# CH32L103F8U-R0.net
KiCad netlist of a schematic drawn in Altium Designer
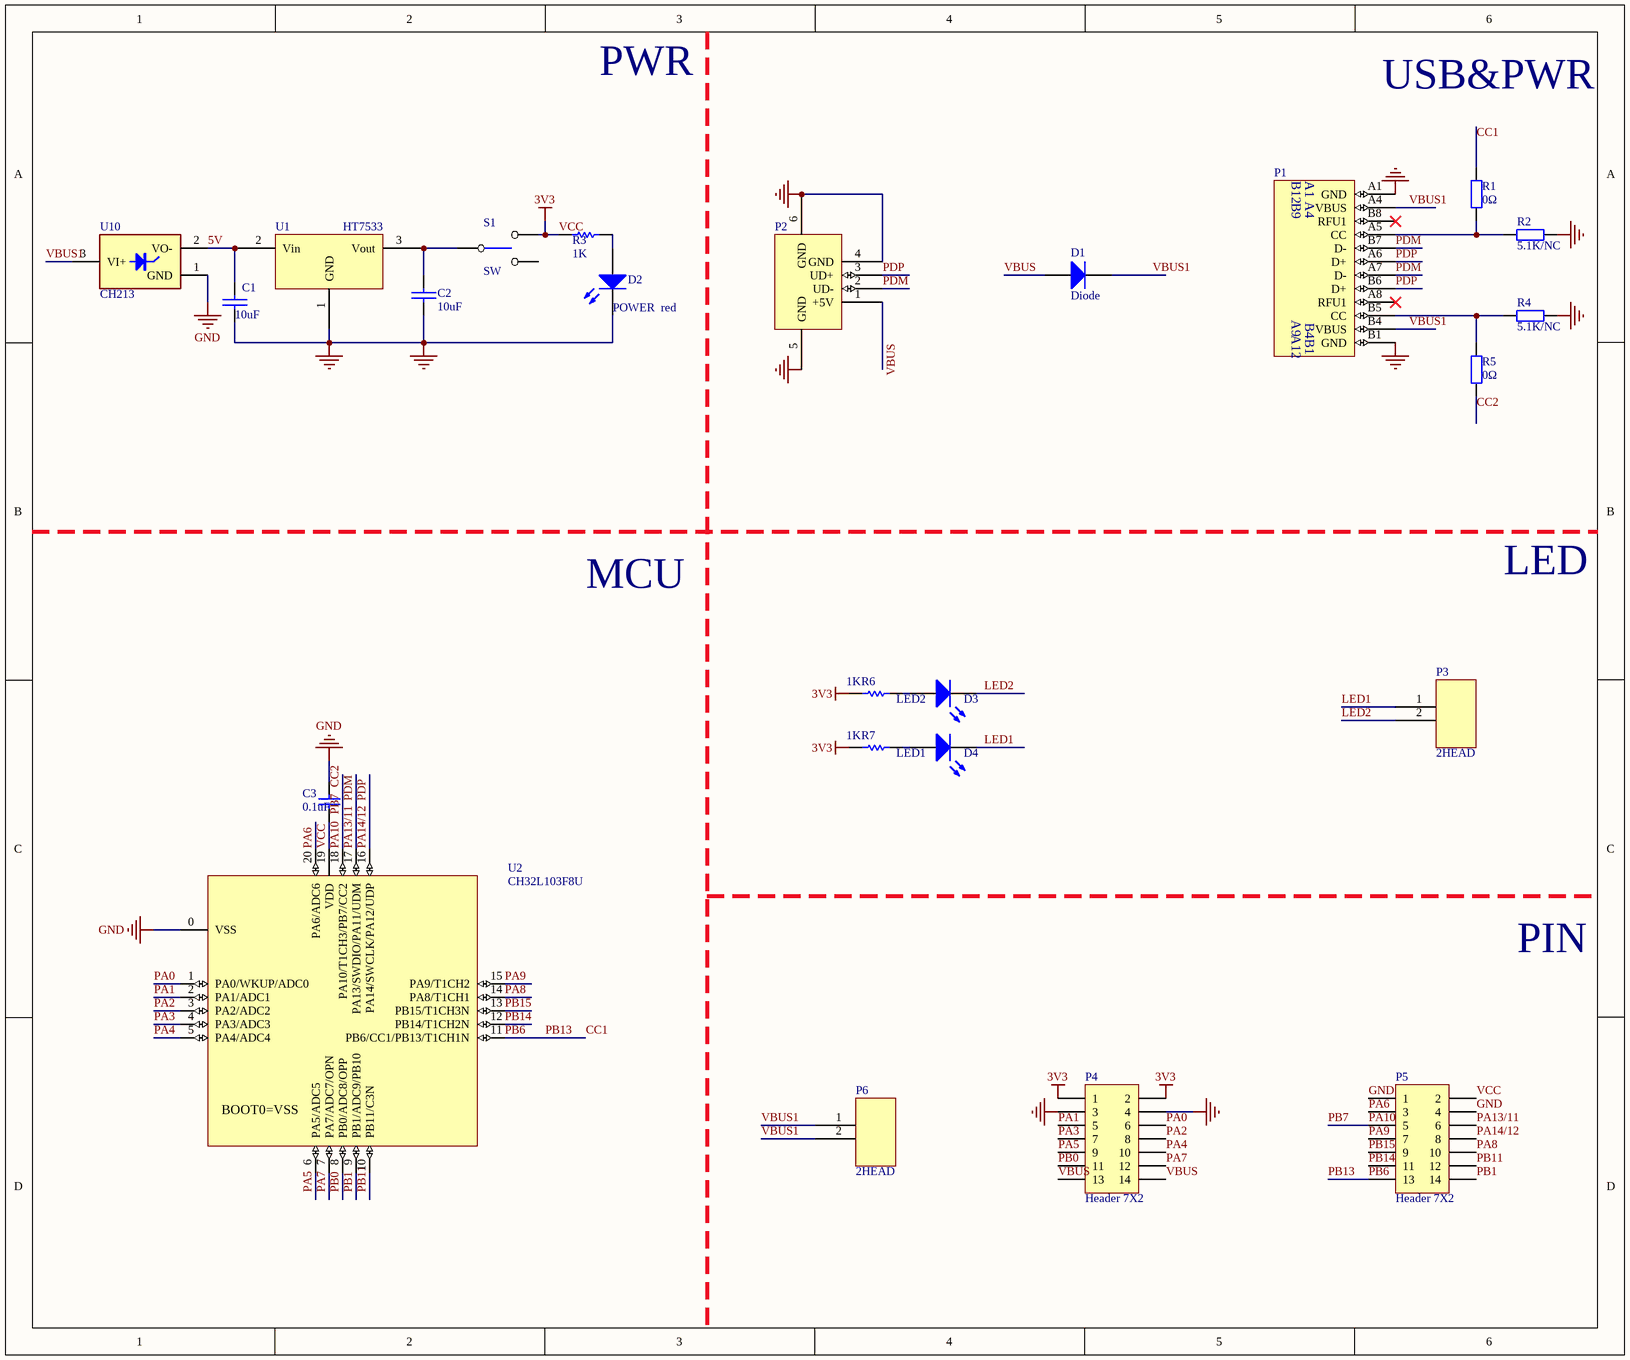
[diagram p0: CH32L103F8U-R0.SchDoc]

(export (version "E")
  (design (tool "Eeschema 10.0.6"))
  (components
    (comp (ref "C1")
      (value "10uF")
      (footprint "0603_C")
      (description "Capacitor")
      (libsource (lib "*") (part "CAP"))
    )
    (comp (ref "C2")
      (value "10uF")
      (footprint "0603_C")
      (description "Capacitor")
      (libsource (lib "*") (part "CAP"))
    )
    (comp (ref "C3")
      (value "0.1uF")
      (footprint "0603_C")
      (description "Capacitor")
      (fields (field (name "PUBLISHER") "Altium Limited"))
      (libsource (lib "*") (part "Cap"))
    )
    (comp (ref "D1")
      (value "Diode")
      (footprint "SOD-123")
      (description "Default Diode")
      (fields (field (name "PUBLISHER") "Altium Limited"))
      (libsource (lib "Miscellaneous Devices") (part "Diode"))
    )
    (comp (ref "D2")
      (value "POWER  red")
      (footprint "0603+")
      (description "Typical INFRARED GaAs LED")
      (fields (field (name "PUBLISHER") "Altium Limited"))
      (libsource (lib "*") (part "LED0"))
    )
    (comp (ref "D3")
      (value "LED2")
      (footprint "0603+")
      (description "Typical INFRARED GaAs LED")
      (fields (field (name "PUBLISHER") "Altium Limited"))
      (libsource (lib "*") (part "LED0"))
    )
    (comp (ref "D4")
      (value "LED1")
      (footprint "0603+")
      (description "Typical INFRARED GaAs LED")
      (fields (field (name "PUBLISHER") "Altium Limited"))
      (libsource (lib "*") (part "LED0"))
    )
    (comp (ref "P1")
      (value "TYPE-C")
      (footprint "TYPE-C-Receptacle-2.0")
      (libsource (lib "*") (part "TYPE-C1"))
    )
    (comp (ref "P2")
      (value "USB_A")
      (footprint "USBAF")
      (description "USB Port")
      (libsource (lib "*") (part "USB"))
    )
    (comp (ref "P3") (value "2HEAD") (footprint "SIP2-2.54mm") (libsource (lib "*") (part "2HEAD")))
    (comp (ref "P4")
      (value "Header 7X2")
      (footprint "IDC14-2.54mm")
      (description "Header, 7-Pin, Dual row")
      (fields (field (name "PUBLISHER") "Altium Limited"))
      (libsource (lib "Miscellaneous Connectors") (part "Header 7X2"))
    )
    (comp (ref "P5")
      (value "Header 7X2")
      (footprint "IDC14-2.54mm")
      (description "Header, 7-Pin, Dual row")
      (fields (field (name "PUBLISHER") "Altium Limited"))
      (libsource (lib "Miscellaneous Connectors") (part "Header 7X2"))
    )
    (comp (ref "P6") (value "2HEAD") (footprint "SIP2-2.54mm") (libsource (lib "*") (part "2HEAD")))
    (comp (ref "R1")
      (value "0Ω")
      (footprint "0603")
      (description "Resistor")
      (libsource (lib "") (part "Res2_1"))
    )
    (comp (ref "R2")
      (value "5.1K/NC")
      (footprint "0603")
      (description "Resistor")
      (libsource (lib "Miscellaneous Devices") (part "Res2"))
    )
    (comp (ref "R3")
      (value "1K")
      (footprint "0603")
      (description "Semiconductor Resistor")
      (libsource (lib "*") (part "Res Semi"))
    )
    (comp (ref "R4")
      (value "5.1K/NC")
      (footprint "0603")
      (description "Resistor")
      (libsource (lib "Miscellaneous Devices") (part "Res2"))
    )
    (comp (ref "R5")
      (value "0Ω")
      (footprint "0603")
      (description "Resistor")
      (libsource (lib "") (part "Res2_1"))
    )
    (comp (ref "R6")
      (value "1K")
      (footprint "0603")
      (description "Semiconductor Resistor")
      (libsource (lib "*") (part "Res Semi"))
    )
    (comp (ref "R7")
      (value "1K")
      (footprint "0603")
      (description "Semiconductor Resistor")
      (libsource (lib "*") (part "Res Semi"))
    )
    (comp (ref "S1") (value "SW") (footprint "SW1") (libsource (lib "*") (part "SW")))
    (comp (ref "U1")
      (value "HT7533")
      (footprint "SOT-89")
      (libsource (lib "wch_sch_others") (part "1117-3.3V"))
    )
    (comp (ref "U2")
      (value "CH32L103F8U")
      (footprint "QFN20_3X3")
      (description "RISC-V LMD-MCU, 96MHz, USB, Type-C/PD-5K1, CAN, OPA, lower power")
      (libsource (lib "CHXXX") (part "CH32L103F8U"))
    )
    (comp (ref "U10")
      (value "CH213")
      (footprint "SOT-23-3")
      (description "Ideal Diode 5V*1A")
      (libsource (lib "CHXXX") (part "CH213E"))
    )
  )
  (nets
    (net (code "1") (name "/5V") (class "Default")
      (node (ref "C1") (pin "1") (pinfunction "1_1") (pintype "passive"))
      (node (ref "U1") (pin "2") (pinfunction "Vin_2") (pintype "passive"))
      (node (ref "U10") (pin "2") (pinfunction "VO-_2") (pintype "power_in"))
    )
    (net (code "3") (name "/CC1") (class "Default")
      (node (ref "P5") (pin "13") (pinfunction "13_13") (pintype "passive"))
      (node (ref "R1") (pin "2") (pinfunction "2_2") (pintype "passive"))
      (node (ref "U2") (pin "11") (pinfunction "PB6/CC1/PB13/T1CH1N_11") (pintype "bidirectional"))
    )
    (net (code "4") (name "/CC2") (class "Default")
      (node (ref "P5") (pin "5") (pinfunction "5_5") (pintype "passive"))
      (node (ref "R5") (pin "1") (pinfunction "1_1") (pintype "passive"))
      (node (ref "U2") (pin "18") (pinfunction "PA10/T1CH3/PB7/CC2_18") (pintype "bidirectional"))
    )
    (net (code "5") (name "/LED1") (class "Default")
      (node (ref "D4") (pin "2") (pinfunction "K_2") (pintype "passive"))
      (node (ref "P3") (pin "1") (pintype "passive"))
    )
    (net (code "6") (name "/LED2") (class "Default")
      (node (ref "D3") (pin "2") (pinfunction "K_2") (pintype "passive"))
      (node (ref "P3") (pin "2") (pintype "passive"))
    )
    (net (code "7") (name "/PA0") (class "Default")
      (node (ref "P4") (pin "6") (pinfunction "6_6") (pintype "passive"))
      (node (ref "U2") (pin "1") (pinfunction "PA0/WKUP/ADC0_1") (pintype "bidirectional"))
    )
    (net (code "8") (name "/PA1") (class "Default")
      (node (ref "P4") (pin "5") (pinfunction "5_5") (pintype "passive"))
      (node (ref "U2") (pin "2") (pinfunction "PA1/ADC1_2") (pintype "bidirectional"))
    )
    (net (code "9") (name "/PA2") (class "Default")
      (node (ref "P4") (pin "8") (pinfunction "8_8") (pintype "passive"))
      (node (ref "U2") (pin "3") (pinfunction "PA2/ADC2_3") (pintype "bidirectional"))
    )
    (net (code "10") (name "/PA3") (class "Default")
      (node (ref "P4") (pin "7") (pinfunction "7_7") (pintype "passive"))
      (node (ref "U2") (pin "4") (pinfunction "PA3/ADC3_4") (pintype "bidirectional"))
    )
    (net (code "11") (name "/PA4") (class "Default")
      (node (ref "P4") (pin "10") (pinfunction "10_10") (pintype "passive"))
      (node (ref "U2") (pin "5") (pinfunction "PA4/ADC4_5") (pintype "bidirectional"))
    )
    (net (code "12") (name "/PA5") (class "Default")
      (node (ref "P4") (pin "9") (pinfunction "9_9") (pintype "passive"))
      (node (ref "U2") (pin "6") (pinfunction "PA5/ADC5_6") (pintype "bidirectional"))
    )
    (net (code "13") (name "/PA6") (class "Default")
      (node (ref "P5") (pin "3") (pinfunction "3_3") (pintype "passive"))
      (node (ref "U2") (pin "20") (pinfunction "PA6/ADC6_20") (pintype "bidirectional"))
    )
    (net (code "14") (name "/PA7") (class "Default")
      (node (ref "P4") (pin "12") (pinfunction "12_12") (pintype "passive"))
      (node (ref "U2") (pin "7") (pinfunction "PA7/ADC7/OPN_7") (pintype "bidirectional"))
    )
    (net (code "15") (name "/PA8") (class "Default")
      (node (ref "P5") (pin "10") (pinfunction "10_10") (pintype "passive"))
      (node (ref "U2") (pin "14") (pinfunction "PA8/T1CH1_14") (pintype "bidirectional"))
    )
    (net (code "16") (name "/PA9") (class "Default")
      (node (ref "P5") (pin "7") (pinfunction "7_7") (pintype "passive"))
      (node (ref "U2") (pin "15") (pinfunction "PA9/T1CH2_15") (pintype "bidirectional"))
    )
    (net (code "17") (name "/PA13{slash}11") (class "Default")
      (node (ref "P1") (pin "A7") (pinfunction "D-_A7") (pintype "bidirectional"))
      (node (ref "P1") (pin "B7") (pinfunction "D-_B7") (pintype "bidirectional"))
      (node (ref "P2") (pin "2") (pinfunction "UD-_2") (pintype "bidirectional"))
      (node (ref "P5") (pin "6") (pinfunction "6_6") (pintype "passive"))
      (node (ref "U2") (pin "17") (pinfunction "PA13/SWDIO/PA11/UDM_17") (pintype "bidirectional"))
    )
    (net (code "18") (name "/PA14{slash}12") (class "Default")
      (node (ref "P1") (pin "A6") (pinfunction "D+_A6") (pintype "bidirectional"))
      (node (ref "P1") (pin "B6") (pinfunction "D+_B6") (pintype "bidirectional"))
      (node (ref "P2") (pin "3") (pinfunction "UD+_3") (pintype "bidirectional"))
      (node (ref "P5") (pin "8") (pinfunction "8_8") (pintype "passive"))
      (node (ref "U2") (pin "16") (pinfunction "PA14/SWCLK/PA12/UDP_16") (pintype "bidirectional"))
    )
    (net (code "19") (name "/PB0") (class "Default")
      (node (ref "P4") (pin "11") (pinfunction "11_11") (pintype "passive"))
      (node (ref "U2") (pin "8") (pinfunction "PB0/ADC8/OPP_8") (pintype "bidirectional"))
    )
    (net (code "20") (name "/PB1") (class "Default")
      (node (ref "P5") (pin "14") (pinfunction "14_14") (pintype "passive"))
      (node (ref "U2") (pin "9") (pinfunction "PB1/ADC9/PB10_9") (pintype "bidirectional"))
    )
    (net (code "21") (name "/PB11") (class "Default")
      (node (ref "P5") (pin "12") (pinfunction "12_12") (pintype "passive"))
      (node (ref "U2") (pin "10") (pinfunction "PB11/C3N_10") (pintype "bidirectional"))
    )
    (net (code "22") (name "/PB14") (class "Default")
      (node (ref "P5") (pin "11") (pinfunction "11_11") (pintype "passive"))
      (node (ref "U2") (pin "12") (pinfunction "PB14/T1CH2N_12") (pintype "bidirectional"))
    )
    (net (code "23") (name "/PB15") (class "Default")
      (node (ref "P5") (pin "9") (pinfunction "9_9") (pintype "passive"))
      (node (ref "U2") (pin "13") (pinfunction "PB15/T1CH3N_13") (pintype "bidirectional"))
    )
    (net (code "24") (name "/VBUS") (class "Default")
      (node (ref "D1") (pin "1") (pinfunction "A_1") (pintype "passive"))
      (node (ref "P2") (pin "1") (pinfunction "+5V_1") (pintype "power_in"))
      (node (ref "P4") (pin "13") (pinfunction "13_13") (pintype "passive"))
      (node (ref "P4") (pin "14") (pinfunction "14_14") (pintype "passive"))
    )
    (net (code "25") (name "/VBUS1") (class "Default")
      (node (ref "D1") (pin "2") (pinfunction "K_2") (pintype "passive"))
      (node (ref "P1") (pin "A4") (pinfunction "VBUS_A4") (pintype "bidirectional"))
      (node (ref "P1") (pin "B4") (pinfunction "VBUS_B4") (pintype "bidirectional"))
      (node (ref "P6") (pin "1") (pintype "passive"))
      (node (ref "P6") (pin "2") (pintype "passive"))
      (node (ref "U10") (pin "3") (pinfunction "VI+_3") (pintype "power_in"))
    )
    (net (code "26") (name "3V3") (class "Default")
      (node (ref "C3") (pin "1") (pinfunction "1_1") (pintype "passive"))
      (node (ref "P4") (pin "1") (pinfunction "1_1") (pintype "passive"))
      (node (ref "P4") (pin "2") (pinfunction "2_2") (pintype "passive"))
      (node (ref "P5") (pin "2") (pinfunction "2_2") (pintype "passive"))
      (node (ref "R3") (pin "2") (pinfunction "2_2") (pintype "passive"))
      (node (ref "R6") (pin "1") (pinfunction "1_1") (pintype "passive"))
      (node (ref "R7") (pin "1") (pinfunction "1_1") (pintype "passive"))
      (node (ref "S1") (pin "3") (pinfunction "3_3") (pintype "passive"))
      (node (ref "U2") (pin "19") (pinfunction "VDD_19") (pintype "power_in"))
    )
    (net (code "27") (name "GND") (class "Default")
      (node (ref "C1") (pin "2") (pinfunction "2_2") (pintype "passive"))
      (node (ref "C2") (pin "2") (pinfunction "2_2") (pintype "passive"))
      (node (ref "C3") (pin "2") (pinfunction "2_2") (pintype "passive"))
      (node (ref "D2") (pin "2") (pinfunction "K_2") (pintype "passive"))
      (node (ref "P1") (pin "A1") (pinfunction "GND_A1") (pintype "bidirectional"))
      (node (ref "P1") (pin "B1") (pinfunction "GND_B1") (pintype "bidirectional"))
      (node (ref "P2") (pin "4") (pinfunction "GND_4") (pintype "power_in"))
      (node (ref "P2") (pin "5") (pinfunction "GND_5") (pintype "power_in"))
      (node (ref "P2") (pin "6") (pinfunction "GND_6") (pintype "power_in"))
      (node (ref "P4") (pin "3") (pinfunction "3_3") (pintype "passive"))
      (node (ref "P4") (pin "4") (pinfunction "4_4") (pintype "passive"))
      (node (ref "P5") (pin "1") (pinfunction "1_1") (pintype "passive"))
      (node (ref "P5") (pin "4") (pinfunction "4_4") (pintype "passive"))
      (node (ref "R2") (pin "2") (pinfunction "2_2") (pintype "passive"))
      (node (ref "R4") (pin "2") (pinfunction "2_2") (pintype "passive"))
      (node (ref "U1") (pin "1") (pinfunction "GND_1") (pintype "passive"))
      (node (ref "U10") (pin "1") (pinfunction "GND_1") (pintype "power_in"))
      (node (ref "U2") (pin "0") (pinfunction "VSS_0") (pintype "power_in"))
    )
    (net (code "28") (name "Net-(D2-A)") (class "Default")
      (node (ref "D2") (pin "1") (pinfunction "A_1") (pintype "passive"))
      (node (ref "R3") (pin "1") (pinfunction "1_1") (pintype "passive"))
    )
    (net (code "29") (name "Net-(D3-A)") (class "Default")
      (node (ref "D3") (pin "1") (pinfunction "A_1") (pintype "passive"))
      (node (ref "R6") (pin "2") (pinfunction "2_2") (pintype "passive"))
    )
    (net (code "30") (name "Net-(D4-A)") (class "Default")
      (node (ref "D4") (pin "1") (pinfunction "A_1") (pintype "passive"))
      (node (ref "R7") (pin "2") (pinfunction "2_2") (pintype "passive"))
    )
    (net (code "31") (name "Net-(P1-CC-PadA5)") (class "Default")
      (node (ref "P1") (pin "A5") (pinfunction "CC_A5") (pintype "bidirectional"))
      (node (ref "R1") (pin "1") (pinfunction "1_1") (pintype "passive"))
      (node (ref "R2") (pin "1") (pinfunction "1_1") (pintype "passive"))
    )
    (net (code "32") (name "Net-(P1-CC-PadB5)") (class "Default")
      (node (ref "P1") (pin "B5") (pinfunction "CC_B5") (pintype "bidirectional"))
      (node (ref "R4") (pin "1") (pinfunction "1_1") (pintype "passive"))
      (node (ref "R5") (pin "2") (pinfunction "2_2") (pintype "passive"))
    )
    (net (code "33") (name "Net-(U1-Vout)") (class "Default")
      (node (ref "C2") (pin "1") (pinfunction "1_1") (pintype "passive"))
      (node (ref "S1") (pin "1") (pinfunction "1_1") (pintype "passive"))
      (node (ref "U1") (pin "3") (pinfunction "Vout_3") (pintype "passive"))
    )
    (net (code "34") (name "unconnected-(P1-RFU1-PadA8)") (class "Default")
      (node (ref "P1") (pin "A8") (pinfunction "RFU1_A8") (pintype "bidirectional+no_connect"))
    )
    (net (code "35") (name "unconnected-(P1-RFU1-PadB8)") (class "Default")
      (node (ref "P1") (pin "B8") (pinfunction "RFU1_B8") (pintype "bidirectional+no_connect"))
    )
    (net (code "36") (name "unconnected-(S1-Pad2)") (class "Default")
      (node (ref "S1") (pin "2") (pinfunction "2_2") (pintype "passive"))
    )
  )
)
